# schema.net
KiCad netlist of a schematic drawn in EAGLE
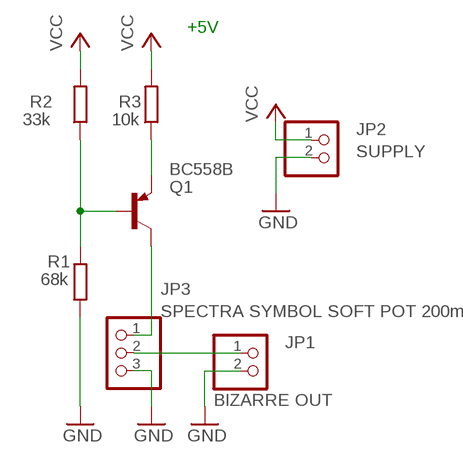
[diagram p0: schematic, sheet 1]

(export (version "E")
  (design (tool "Eeschema 10.0.6"))
  (components
    (comp (ref "JP1")
      (value "BIZARRE OUT")
      (footprint "eagle-import:1X02")
      (libsource (lib "eagle-import") (part "PINHD-1X2"))
    )
    (comp (ref "JP2")
      (value "SUPPLY")
      (footprint "eagle-import:1X02")
      (libsource (lib "eagle-import") (part "PINHD-1X2"))
    )
    (comp (ref "JP3")
      (value "SPECTRA SYMBOL SOFT POT 200mm")
      (footprint "eagle-import:1X03")
      (libsource (lib "eagle-import") (part "PINHD-1X3"))
    )
    (comp (ref "Q1")
      (value "BC558B")
      (footprint "eagle-import:TO92-EBC")
      (libsource (lib "eagle-import") (part "BC558B"))
    )
    (comp (ref "R1")
      (value "68k")
      (footprint "eagle-import:0309_10")
      (libsource (lib "eagle-import") (part "R-EU_0309/10"))
    )
    (comp (ref "R2")
      (value "33k")
      (footprint "eagle-import:0309_10")
      (libsource (lib "eagle-import") (part "R-EU_0309/10"))
    )
    (comp (ref "R3")
      (value "10k")
      (footprint "eagle-import:0309_10")
      (libsource (lib "eagle-import") (part "R-EU_0309/10"))
    )
  )
  (nets
    (net (code "1") (name "GND") (class "Default")
      (node (ref "JP1") (pin "2") (pinfunction "2_2") (pintype "passive"))
      (node (ref "JP2") (pin "2") (pinfunction "2_2") (pintype "passive"))
      (node (ref "JP3") (pin "3") (pinfunction "3_3") (pintype "passive"))
      (node (ref "R1") (pin "1") (pinfunction "1_1") (pintype "passive"))
    )
    (net (code "2") (name "Net-(JP1-Pad1)") (class "Default")
      (node (ref "JP1") (pin "1") (pinfunction "1_1") (pintype "passive"))
      (node (ref "JP3") (pin "2") (pinfunction "2_2") (pintype "passive"))
    )
    (net (code "3") (name "Net-(JP3-Pad1)") (class "Default")
      (node (ref "JP3") (pin "1") (pinfunction "1_1") (pintype "passive"))
      (node (ref "Q1") (pin "C") (pinfunction "C_C") (pintype "passive"))
    )
    (net (code "4") (name "Net-(Q1-PadB)") (class "Default")
      (node (ref "Q1") (pin "B") (pinfunction "B_B") (pintype "passive"))
      (node (ref "R1") (pin "2") (pinfunction "2_2") (pintype "passive"))
      (node (ref "R2") (pin "1") (pinfunction "1_1") (pintype "passive"))
    )
    (net (code "5") (name "Net-(Q1-PadE)") (class "Default")
      (node (ref "Q1") (pin "E") (pinfunction "E_E") (pintype "passive"))
      (node (ref "R3") (pin "1") (pinfunction "1_1") (pintype "passive"))
    )
    (net (code "6") (name "VCC") (class "Default")
      (node (ref "JP2") (pin "1") (pinfunction "1_1") (pintype "passive"))
      (node (ref "R2") (pin "2") (pinfunction "2_2") (pintype "passive"))
      (node (ref "R3") (pin "2") (pinfunction "2_2") (pintype "passive"))
    )
  )
)
